# solar.net
KiCad netlist of a schematic drawn in Altium Designer
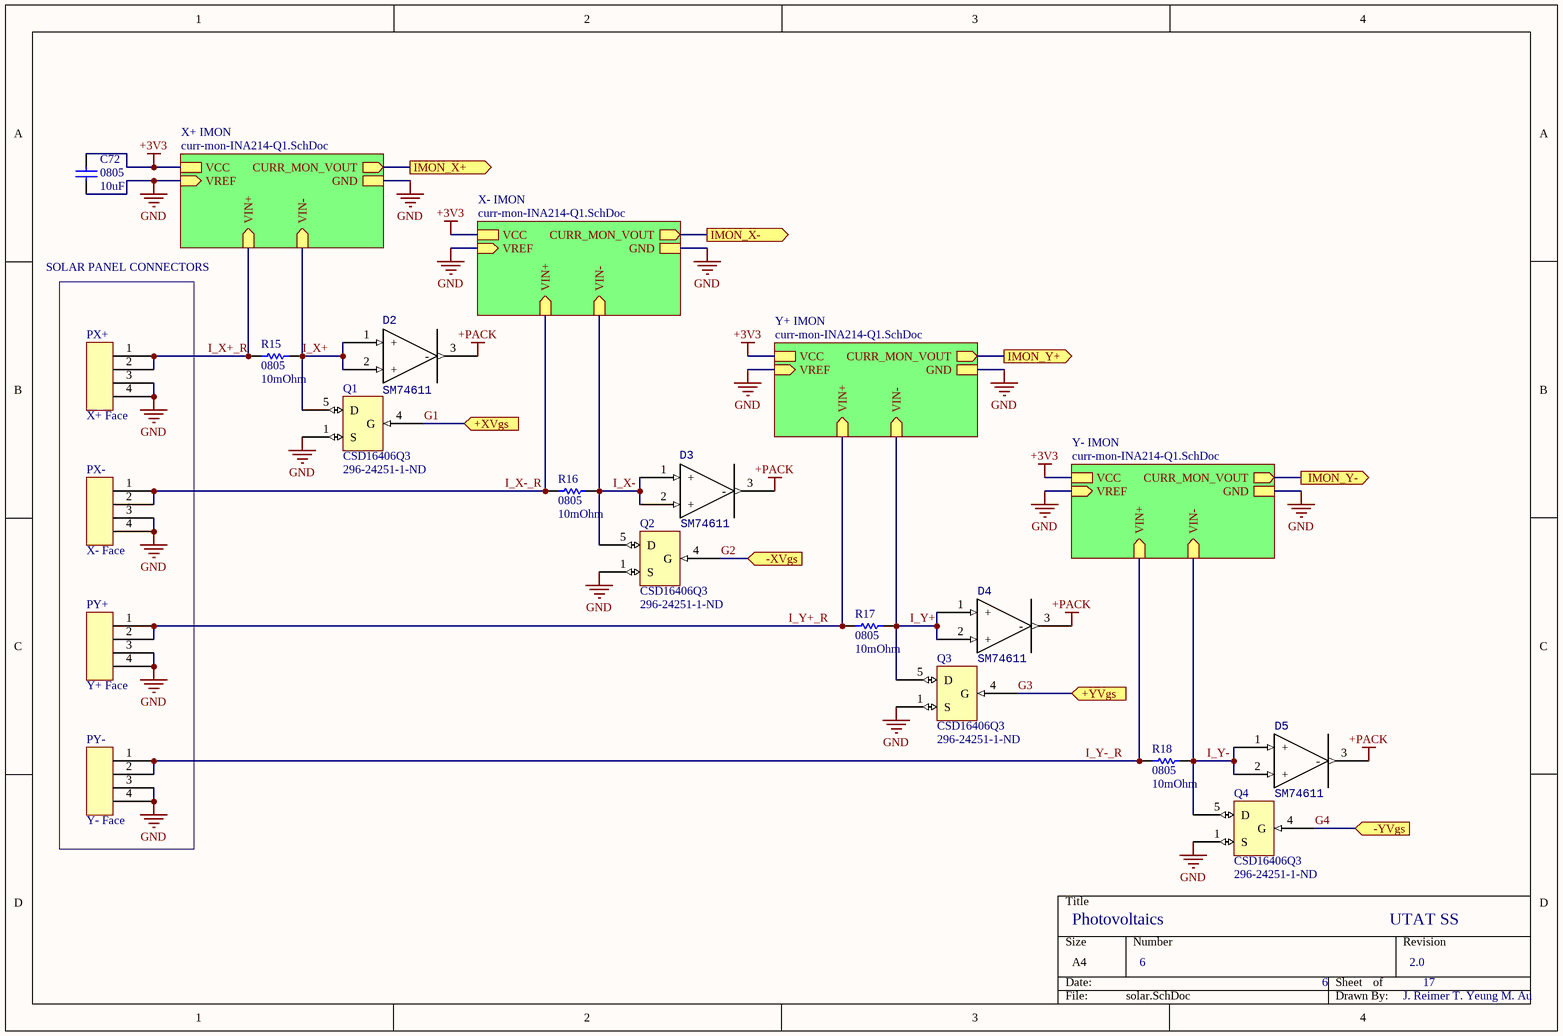
[diagram p0: solar.SchDoc]

(export (version "E")
  (design (tool "Eeschema 10.0.6"))
  (components
    (comp (ref "C72")
      (value "0805")
      (footprint "CAP0805R")
      (description "0805 capacitor")
      (fields (field (name "ALTIUM_VALUE") "10uF"))
      (libsource (lib "heron-general") (part "CAP0805"))
    )
    (comp (ref "D2")
      (value "SM74611")
      (footprint "TO254P1435X464-3N")
      (description "PV Diode")
      (fields
        (field (name "MANUFACTURER") "Texas Instruments")
        (field (name "MANUFACTURER PART NUMBER") "SM74611KTTR")
      )
      (libsource (lib "heron-general") (part "SM74611"))
    )
    (comp (ref "D3")
      (value "SM74611")
      (footprint "TO254P1435X464-3N")
      (description "PV Diode")
      (fields
        (field (name "MANUFACTURER") "Texas Instruments")
        (field (name "MANUFACTURER PART NUMBER") "SM74611KTTR")
      )
      (libsource (lib "heron-general") (part "SM74611"))
    )
    (comp (ref "D4")
      (value "SM74611")
      (footprint "TO254P1435X464-3N")
      (description "PV Diode")
      (fields
        (field (name "MANUFACTURER") "Texas Instruments")
        (field (name "MANUFACTURER PART NUMBER") "SM74611KTTR")
      )
      (libsource (lib "heron-general") (part "SM74611"))
    )
    (comp (ref "D5")
      (value "SM74611")
      (footprint "TO254P1435X464-3N")
      (description "PV Diode")
      (fields
        (field (name "MANUFACTURER") "Texas Instruments")
        (field (name "MANUFACTURER PART NUMBER") "SM74611KTTR")
      )
      (libsource (lib "heron-general") (part "SM74611"))
    )
    (comp (ref "PX+")
      (value "DF13A-4P-1.25H(51)")
      (footprint "DF13A-4P-1.25H(51)")
      (description "4 pos DF13 right angle surface mount connector")
      (libsource (lib "heron-general") (part "DF13A-4P-1.25H(51)"))
    )
    (comp (ref "PX-")
      (value "DF13A-4P-1.25H(51)")
      (footprint "DF13A-4P-1.25H(51)")
      (description "4 pos DF13 right angle surface mount connector")
      (libsource (lib "heron-general") (part "DF13A-4P-1.25H(51)"))
    )
    (comp (ref "PY+")
      (value "DF13A-4P-1.25H(51)")
      (footprint "DF13A-4P-1.25H(51)")
      (description "4 pos DF13 right angle surface mount connector")
      (libsource (lib "heron-general") (part "DF13A-4P-1.25H(51)"))
    )
    (comp (ref "PY-")
      (value "DF13A-4P-1.25H(51)")
      (footprint "DF13A-4P-1.25H(51)")
      (description "4 pos DF13 right angle surface mount connector")
      (libsource (lib "heron-general") (part "DF13A-4P-1.25H(51)"))
    )
    (comp (ref "Q1")
      (value "CSD16406Q3")
      (footprint "CSD16406Q3")
      (description "Power MOSFET")
      (fields
        (field (name "MANUFACTURER") "Texas Instruments")
        (field (name "SUPPLIER PART NUMBER 1") "296-24251-1-ND")
      )
      (libsource (lib "heron-general") (part "CSD16406Q3"))
    )
    (comp (ref "Q2")
      (value "CSD16406Q3")
      (footprint "CSD16406Q3")
      (description "Power MOSFET")
      (fields
        (field (name "MANUFACTURER") "Texas Instruments")
        (field (name "SUPPLIER PART NUMBER 1") "296-24251-1-ND")
      )
      (libsource (lib "heron-general") (part "CSD16406Q3"))
    )
    (comp (ref "Q3")
      (value "CSD16406Q3")
      (footprint "CSD16406Q3")
      (description "Power MOSFET")
      (fields
        (field (name "MANUFACTURER") "Texas Instruments")
        (field (name "SUPPLIER PART NUMBER 1") "296-24251-1-ND")
      )
      (libsource (lib "heron-general") (part "CSD16406Q3"))
    )
    (comp (ref "Q4")
      (value "CSD16406Q3")
      (footprint "CSD16406Q3")
      (description "Power MOSFET")
      (fields
        (field (name "MANUFACTURER") "Texas Instruments")
        (field (name "SUPPLIER PART NUMBER 1") "296-24251-1-ND")
      )
      (libsource (lib "heron-general") (part "CSD16406Q3"))
    )
    (comp (ref "R15")
      (value "0805")
      (footprint "RES0805R")
      (description "0805 resistor")
      (fields
        (field (name "ALTIUM_VALUE") "10mOhm")
        (field (name "MANUFACTURER") "Panasonic")
        (field (name "MANUFACTURER PART NUMBER") "ERJ-8BWJR010V")
      )
      (libsource (lib "heron-general") (part "RES0805"))
    )
    (comp (ref "R16")
      (value "0805")
      (footprint "RES0805R")
      (description "0805 resistor")
      (fields
        (field (name "ALTIUM_VALUE") "10mOhm")
        (field (name "MANUFACTURER") "Panasonic")
        (field (name "MANUFACTURER PART NUMBER") "ERJ-8BWJR010V")
      )
      (libsource (lib "heron-general") (part "RES0805"))
    )
    (comp (ref "R17")
      (value "0805")
      (footprint "RES0805R")
      (description "0805 resistor")
      (fields
        (field (name "ALTIUM_VALUE") "10mOhm")
        (field (name "MANUFACTURER") "Panasonic")
        (field (name "MANUFACTURER PART NUMBER") "ERJ-8BWJR010V")
      )
      (libsource (lib "heron-general") (part "RES0805"))
    )
    (comp (ref "R18")
      (value "0805")
      (footprint "RES0805R")
      (description "0805 resistor")
      (fields
        (field (name "ALTIUM_VALUE") "10mOhm")
        (field (name "MANUFACTURER") "Panasonic")
        (field (name "MANUFACTURER PART NUMBER") "ERJ-8BWJR010V")
      )
      (libsource (lib "heron-general") (part "RES0805"))
    )
  )
  (nets
    (net (code "1") (name "+3V3") (class "Default")
      (node (ref "C72") (pin "2") (pinfunction "2_2") (pintype "passive"))
    )
    (net (code "2") (name "+PACK") (class "Default")
      (node (ref "D2") (pin "3") (pinfunction "-_3") (pintype "output"))
      (node (ref "D3") (pin "3") (pinfunction "-_3") (pintype "output"))
      (node (ref "D4") (pin "3") (pinfunction "-_3") (pintype "output"))
      (node (ref "D5") (pin "3") (pinfunction "-_3") (pintype "output"))
    )
    (net (code "3") (name "/G1") (class "Default")
      (node (ref "Q1") (pin "4") (pinfunction "G_4") (pintype "input"))
    )
    (net (code "4") (name "/G2") (class "Default")
      (node (ref "Q2") (pin "4") (pinfunction "G_4") (pintype "input"))
    )
    (net (code "5") (name "/G3") (class "Default")
      (node (ref "Q3") (pin "4") (pinfunction "G_4") (pintype "input"))
    )
    (net (code "6") (name "/G4") (class "Default")
      (node (ref "Q4") (pin "4") (pinfunction "G_4") (pintype "input"))
    )
    (net (code "11") (name "/I_X+") (class "Default")
      (node (ref "D2") (pin "1") (pinfunction "+_1") (pintype "input"))
      (node (ref "D2") (pin "2") (pinfunction "+_2") (pintype "input"))
      (node (ref "Q1") (pin "5") (pinfunction "D_5") (pintype "bidirectional"))
      (node (ref "R15") (pin "2") (pinfunction "2_2") (pintype "passive"))
    )
    (net (code "12") (name "/I_X+_R") (class "Default")
      (node (ref "PX+") (pin "1") (pintype "passive"))
      (node (ref "PX+") (pin "2") (pintype "passive"))
      (node (ref "R15") (pin "1") (pinfunction "1_1") (pintype "passive"))
    )
    (net (code "13") (name "/I_X-") (class "Default")
      (node (ref "D3") (pin "1") (pinfunction "+_1") (pintype "input"))
      (node (ref "D3") (pin "2") (pinfunction "+_2") (pintype "input"))
      (node (ref "Q2") (pin "5") (pinfunction "D_5") (pintype "bidirectional"))
      (node (ref "R16") (pin "2") (pinfunction "2_2") (pintype "passive"))
    )
    (net (code "14") (name "/I_X-_R") (class "Default")
      (node (ref "PX-") (pin "1") (pintype "passive"))
      (node (ref "PX-") (pin "2") (pintype "passive"))
      (node (ref "R16") (pin "1") (pinfunction "1_1") (pintype "passive"))
    )
    (net (code "15") (name "/I_Y+") (class "Default")
      (node (ref "D4") (pin "1") (pinfunction "+_1") (pintype "input"))
      (node (ref "D4") (pin "2") (pinfunction "+_2") (pintype "input"))
      (node (ref "Q3") (pin "5") (pinfunction "D_5") (pintype "bidirectional"))
      (node (ref "R17") (pin "2") (pinfunction "2_2") (pintype "passive"))
    )
    (net (code "16") (name "/I_Y+_R") (class "Default")
      (node (ref "PY+") (pin "1") (pintype "passive"))
      (node (ref "PY+") (pin "2") (pintype "passive"))
      (node (ref "R17") (pin "1") (pinfunction "1_1") (pintype "passive"))
    )
    (net (code "17") (name "/I_Y-") (class "Default")
      (node (ref "D5") (pin "1") (pinfunction "+_1") (pintype "input"))
      (node (ref "D5") (pin "2") (pinfunction "+_2") (pintype "input"))
      (node (ref "Q4") (pin "5") (pinfunction "D_5") (pintype "bidirectional"))
      (node (ref "R18") (pin "2") (pinfunction "2_2") (pintype "passive"))
    )
    (net (code "18") (name "/I_Y-_R") (class "Default")
      (node (ref "PY-") (pin "1") (pintype "passive"))
      (node (ref "PY-") (pin "2") (pintype "passive"))
      (node (ref "R18") (pin "1") (pinfunction "1_1") (pintype "passive"))
    )
    (net (code "19") (name "GND") (class "Default")
      (node (ref "C72") (pin "1") (pinfunction "1_1") (pintype "passive"))
      (node (ref "PX+") (pin "3") (pintype "passive"))
      (node (ref "PX+") (pin "4") (pintype "passive"))
      (node (ref "PX-") (pin "3") (pintype "passive"))
      (node (ref "PX-") (pin "4") (pintype "passive"))
      (node (ref "PY+") (pin "3") (pintype "passive"))
      (node (ref "PY+") (pin "4") (pintype "passive"))
      (node (ref "PY-") (pin "3") (pintype "passive"))
      (node (ref "PY-") (pin "4") (pintype "passive"))
      (node (ref "Q1") (pin "1") (pinfunction "S_1") (pintype "bidirectional"))
      (node (ref "Q2") (pin "1") (pinfunction "S_1") (pintype "bidirectional"))
      (node (ref "Q3") (pin "1") (pinfunction "S_1") (pintype "bidirectional"))
      (node (ref "Q4") (pin "1") (pinfunction "S_1") (pintype "bidirectional"))
    )
  )
)
